# Headers.net
KiCad netlist of a schematic drawn in Altium Designer
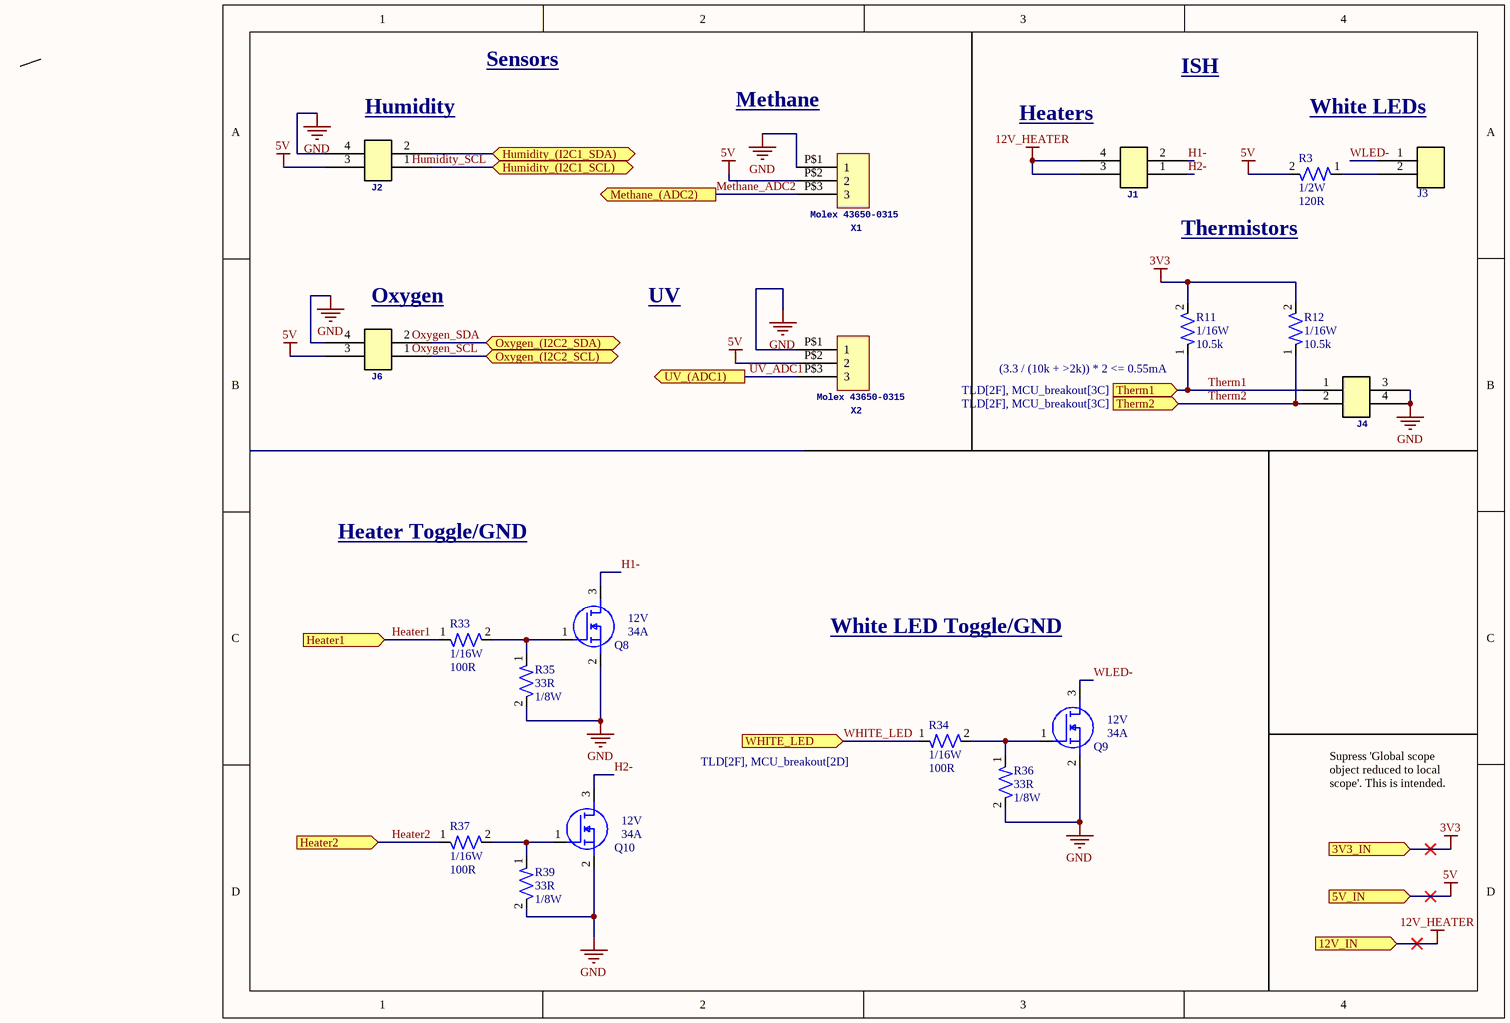
[diagram p0: Headers.SchDoc]

(export (version "E")
  (design (tool "Eeschema 10.0.6"))
  (components
    (comp (ref "J1")
      (value "Molex 43045-0412")
      (footprint "CONN-4POS-0002")
      (description "CONN HEADER VERT 4POS 3MM")
      (libsource (lib "JLC_25") (part "CONN-4POS-0002"))
    )
    (comp (ref "J2")
      (value "Molex 43045-0412")
      (footprint "CONN-4POS-0002")
      (description "CONN HEADER VERT 4POS 3MM")
      (libsource (lib "JLC_25") (part "CONN-4POS-0002"))
    )
    (comp (ref "J3")
      (value "0430450212")
      (footprint "CONN-2POS-0001")
      (description "CONN HEADER VERT 2POS")
      (libsource (lib "JLC_25") (part "CONN-2POS-0001"))
    )
    (comp (ref "J4")
      (value "Molex 43045-0412")
      (footprint "CONN-4POS-0002")
      (description "CONN HEADER VERT 4POS 3MM")
      (libsource (lib "") (part "CONN-4POS-0002_1"))
    )
    (comp (ref "J6")
      (value "Molex 43045-0412")
      (footprint "CONN-4POS-0002")
      (description "CONN HEADER VERT 4POS 3MM")
      (libsource (lib "JLC_25") (part "CONN-4POS-0002"))
    )
    (comp (ref "Q8")
      (value "SI4838BDY-T1-GE3")
      (footprint "SOIC8_NARROW_VIS")
      (description "MOSFET N-CH 12 V 34A (Tc) 2.5W (Ta), 5.7W (Tc) Surface Mount 8-SOIC")
      (libsource (lib "JLC_25") (part "NMOS-34A-0001"))
    )
    (comp (ref "Q9")
      (value "SI4838BDY-T1-GE3")
      (footprint "SOIC8_NARROW_VIS")
      (description "MOSFET N-CH 12 V 34A (Tc) 2.5W (Ta), 5.7W (Tc) Surface Mount 8-SOIC")
      (libsource (lib "JLC_25") (part "NMOS-34A-0001"))
    )
    (comp (ref "Q10")
      (value "SI4838BDY-T1-GE3")
      (footprint "SOIC8_NARROW_VIS")
      (description "MOSFET N-CH 12 V 34A (Tc) 2.5W (Ta), 5.7W (Tc) Surface Mount 8-SOIC")
      (libsource (lib "JLC_25") (part "NMOS-34A-0001"))
    )
    (comp (ref "R3")
      (value "RC1210FR-07120RL")
      (footprint "RES-1210")
      (description "RES 120 OHM 1% 1/2W 1210")
      (fields
        (field (name "TOLERANCE") "1%")
        (field (name "POWER") "1/2W")
        (field (name "RESISTANCE") "120R")
      )
      (libsource (lib "JLC_25") (part "RES-120-0001"))
    )
    (comp (ref "R11")
      (value "RC0402FR-0710K5L")
      (footprint "RES-0402")
      (description "RES 10.5K OHM 1% 1/16W 0402")
      (fields
        (field (name "TOLERANCE") "1%")
        (field (name "POWER") "1/16W")
        (field (name "RESISTANCE") "10.5k")
      )
      (libsource (lib "JLC_25") (part "RES-10.5k-0001"))
    )
    (comp (ref "R12")
      (value "RC0402FR-0710K5L")
      (footprint "RES-0402")
      (description "RES 10.5K OHM 1% 1/16W 0402")
      (fields
        (field (name "TOLERANCE") "1%")
        (field (name "POWER") "1/16W")
        (field (name "RESISTANCE") "10.5k")
      )
      (libsource (lib "JLC_25") (part "RES-10.5k-0001"))
    )
    (comp (ref "R33")
      (value "RC0402FR-07100RL")
      (footprint "RES-0402")
      (description "RES 100 OHM 1% 1/16W 0402")
      (fields
        (field (name "TOLERANCE") "1%")
        (field (name "POWER") "1/16W")
        (field (name "RESISTANCE") "100R")
      )
      (libsource (lib "JLC_25") (part "RES-100-0001"))
    )
    (comp (ref "R34")
      (value "RC0402FR-07100RL")
      (footprint "RES-0402")
      (description "RES 100 OHM 1% 1/16W 0402")
      (fields
        (field (name "TOLERANCE") "1%")
        (field (name "POWER") "1/16W")
        (field (name "RESISTANCE") "100R")
      )
      (libsource (lib "JLC_25") (part "RES-100-0001"))
    )
    (comp (ref "R35")
      (value "RC0402FR-7W33RL")
      (footprint "RES-0402")
      (description "RES 33 OHM 1% 1/8W 0402")
      (fields (field (name "TOLERANCE") "1%") (field (name "RESISTANCE") "33R") (field (name "POWER") "1/8W"))
      (libsource (lib "JLC_25") (part "RES-33-0001"))
    )
    (comp (ref "R36")
      (value "RC0402FR-7W33RL")
      (footprint "RES-0402")
      (description "RES 33 OHM 1% 1/8W 0402")
      (fields (field (name "TOLERANCE") "1%") (field (name "RESISTANCE") "33R") (field (name "POWER") "1/8W"))
      (libsource (lib "JLC_25") (part "RES-33-0001"))
    )
    (comp (ref "R37")
      (value "RC0402FR-07100RL")
      (footprint "RES-0402")
      (description "RES 100 OHM 1% 1/16W 0402")
      (fields
        (field (name "TOLERANCE") "1%")
        (field (name "POWER") "1/16W")
        (field (name "RESISTANCE") "100R")
      )
      (libsource (lib "JLC_25") (part "RES-100-0001"))
    )
    (comp (ref "R39")
      (value "RC0402FR-7W33RL")
      (footprint "RES-0402")
      (description "RES 33 OHM 1% 1/8W 0402")
      (fields (field (name "TOLERANCE") "1%") (field (name "RESISTANCE") "33R") (field (name "POWER") "1/8W"))
      (libsource (lib "JLC_25") (part "RES-33-0001"))
    )
    (comp (ref "X1")
      (value "Molex 43650-0315")
      (footprint "43650-0315")
      (libsource (lib "JLC_25") (part "Micro-Fit Molex 3 Pin Vertical"))
    )
    (comp (ref "X2")
      (value "Molex 43650-0315")
      (footprint "43650-0315")
      (libsource (lib "JLC_25") (part "Micro-Fit Molex 3 Pin Vertical"))
    )
  )
  (nets
    (net (code "1") (name "/H1-") (class "Default")
      (node (ref "J1") (pin "2") (pinfunction "2_2") (pintype "passive"))
      (node (ref "Q8") (pin "3") (pinfunction "D_3") (pintype "passive"))
    )
    (net (code "2") (name "/H2-") (class "Default")
      (node (ref "J1") (pin "1") (pinfunction "1_1") (pintype "passive"))
      (node (ref "Q10") (pin "3") (pinfunction "D_3") (pintype "passive"))
    )
    (net (code "3") (name "/Heater1") (class "Default")
      (node (ref "R33") (pin "1") (pinfunction "1_1") (pintype "passive"))
    )
    (net (code "4") (name "/Heater2") (class "Default")
      (node (ref "R37") (pin "1") (pinfunction "1_1") (pintype "passive"))
    )
    (net (code "5") (name "/Humidity_(I2C1_SCL)") (class "Default")
      (node (ref "J2") (pin "1") (pinfunction "1_1") (pintype "passive"))
    )
    (net (code "6") (name "/Humidity_(I2C1_SDA)") (class "Default")
      (node (ref "J2") (pin "2") (pinfunction "2_2") (pintype "passive"))
    )
    (net (code "8") (name "/Methane_ADC2") (class "Default")
      (node (ref "X1") (pin "P$3") (pinfunction "3_P$3") (pintype "passive"))
    )
    (net (code "9") (name "/Oxygen_(I2C2_SCL)") (class "Default")
      (node (ref "J6") (pin "1") (pinfunction "1_1") (pintype "passive"))
    )
    (net (code "10") (name "/Oxygen_(I2C2_SDA)") (class "Default")
      (node (ref "J6") (pin "2") (pinfunction "2_2") (pintype "passive"))
    )
    (net (code "13") (name "/Therm1") (class "Default")
      (node (ref "J4") (pin "1") (pinfunction "1_1") (pintype "passive"))
      (node (ref "R11") (pin "1") (pinfunction "1_1") (pintype "passive"))
    )
    (net (code "14") (name "/Therm2") (class "Default")
      (node (ref "J4") (pin "2") (pinfunction "2_2") (pintype "passive"))
      (node (ref "R12") (pin "1") (pinfunction "1_1") (pintype "passive"))
    )
    (net (code "15") (name "/UV_ADC1") (class "Default")
      (node (ref "X2") (pin "P$3") (pinfunction "3_P$3") (pintype "passive"))
    )
    (net (code "16") (name "/WHITE_LED") (class "Default")
      (node (ref "R34") (pin "1") (pinfunction "1_1") (pintype "passive"))
    )
    (net (code "17") (name "/WLED-") (class "Default")
      (node (ref "J3") (pin "1") (pinfunction "7_1") (pintype "passive"))
      (node (ref "Q9") (pin "3") (pinfunction "D_3") (pintype "passive"))
    )
    (net (code "18") (name "3V3") (class "Default")
      (node (ref "R11") (pin "2") (pinfunction "2_2") (pintype "passive"))
      (node (ref "R12") (pin "2") (pinfunction "2_2") (pintype "passive"))
    )
    (net (code "19") (name "5V") (class "Default")
      (node (ref "J2") (pin "3") (pinfunction "3_3") (pintype "passive"))
      (node (ref "J6") (pin "3") (pinfunction "3_3") (pintype "passive"))
      (node (ref "R3") (pin "2") (pinfunction "2_2") (pintype "passive"))
      (node (ref "X1") (pin "P$2") (pinfunction "2_P$2") (pintype "passive"))
      (node (ref "X2") (pin "P$2") (pinfunction "2_P$2") (pintype "passive"))
    )
    (net (code "20") (name "12V_HEATER") (class "Default")
      (node (ref "J1") (pin "3") (pinfunction "3_3") (pintype "passive"))
      (node (ref "J1") (pin "4") (pinfunction "4_4") (pintype "passive"))
    )
    (net (code "21") (name "GND") (class "Default")
      (node (ref "J2") (pin "4") (pinfunction "4_4") (pintype "passive"))
      (node (ref "J4") (pin "3") (pinfunction "3_3") (pintype "passive"))
      (node (ref "J4") (pin "4") (pinfunction "4_4") (pintype "passive"))
      (node (ref "J6") (pin "4") (pinfunction "4_4") (pintype "passive"))
      (node (ref "Q10") (pin "2") (pinfunction "S_2") (pintype "passive"))
      (node (ref "Q8") (pin "2") (pinfunction "S_2") (pintype "passive"))
      (node (ref "Q9") (pin "2") (pinfunction "S_2") (pintype "passive"))
      (node (ref "R35") (pin "2") (pinfunction "2_2") (pintype "passive"))
      (node (ref "R36") (pin "2") (pinfunction "2_2") (pintype "passive"))
      (node (ref "R39") (pin "2") (pinfunction "2_2") (pintype "passive"))
      (node (ref "X1") (pin "P$1") (pinfunction "1_P$1") (pintype "passive"))
      (node (ref "X2") (pin "P$1") (pinfunction "1_P$1") (pintype "passive"))
    )
    (net (code "22") (name "Net-(J3-8)") (class "Default")
      (node (ref "J3") (pin "2") (pinfunction "8_2") (pintype "passive"))
      (node (ref "R3") (pin "1") (pinfunction "1_1") (pintype "passive"))
    )
    (net (code "23") (name "Net-(Q8-G)") (class "Default")
      (node (ref "Q8") (pin "1") (pinfunction "G_1") (pintype "passive"))
      (node (ref "R33") (pin "2") (pinfunction "2_2") (pintype "passive"))
      (node (ref "R35") (pin "1") (pinfunction "1_1") (pintype "passive"))
    )
    (net (code "24") (name "Net-(Q9-G)") (class "Default")
      (node (ref "Q9") (pin "1") (pinfunction "G_1") (pintype "passive"))
      (node (ref "R34") (pin "2") (pinfunction "2_2") (pintype "passive"))
      (node (ref "R36") (pin "1") (pinfunction "1_1") (pintype "passive"))
    )
    (net (code "25") (name "Net-(Q10-G)") (class "Default")
      (node (ref "Q10") (pin "1") (pinfunction "G_1") (pintype "passive"))
      (node (ref "R37") (pin "2") (pinfunction "2_2") (pintype "passive"))
      (node (ref "R39") (pin "1") (pinfunction "1_1") (pintype "passive"))
    )
  )
)
